# MKRCANShieldV2_0.net
KiCad netlist of a schematic drawn in EAGLE
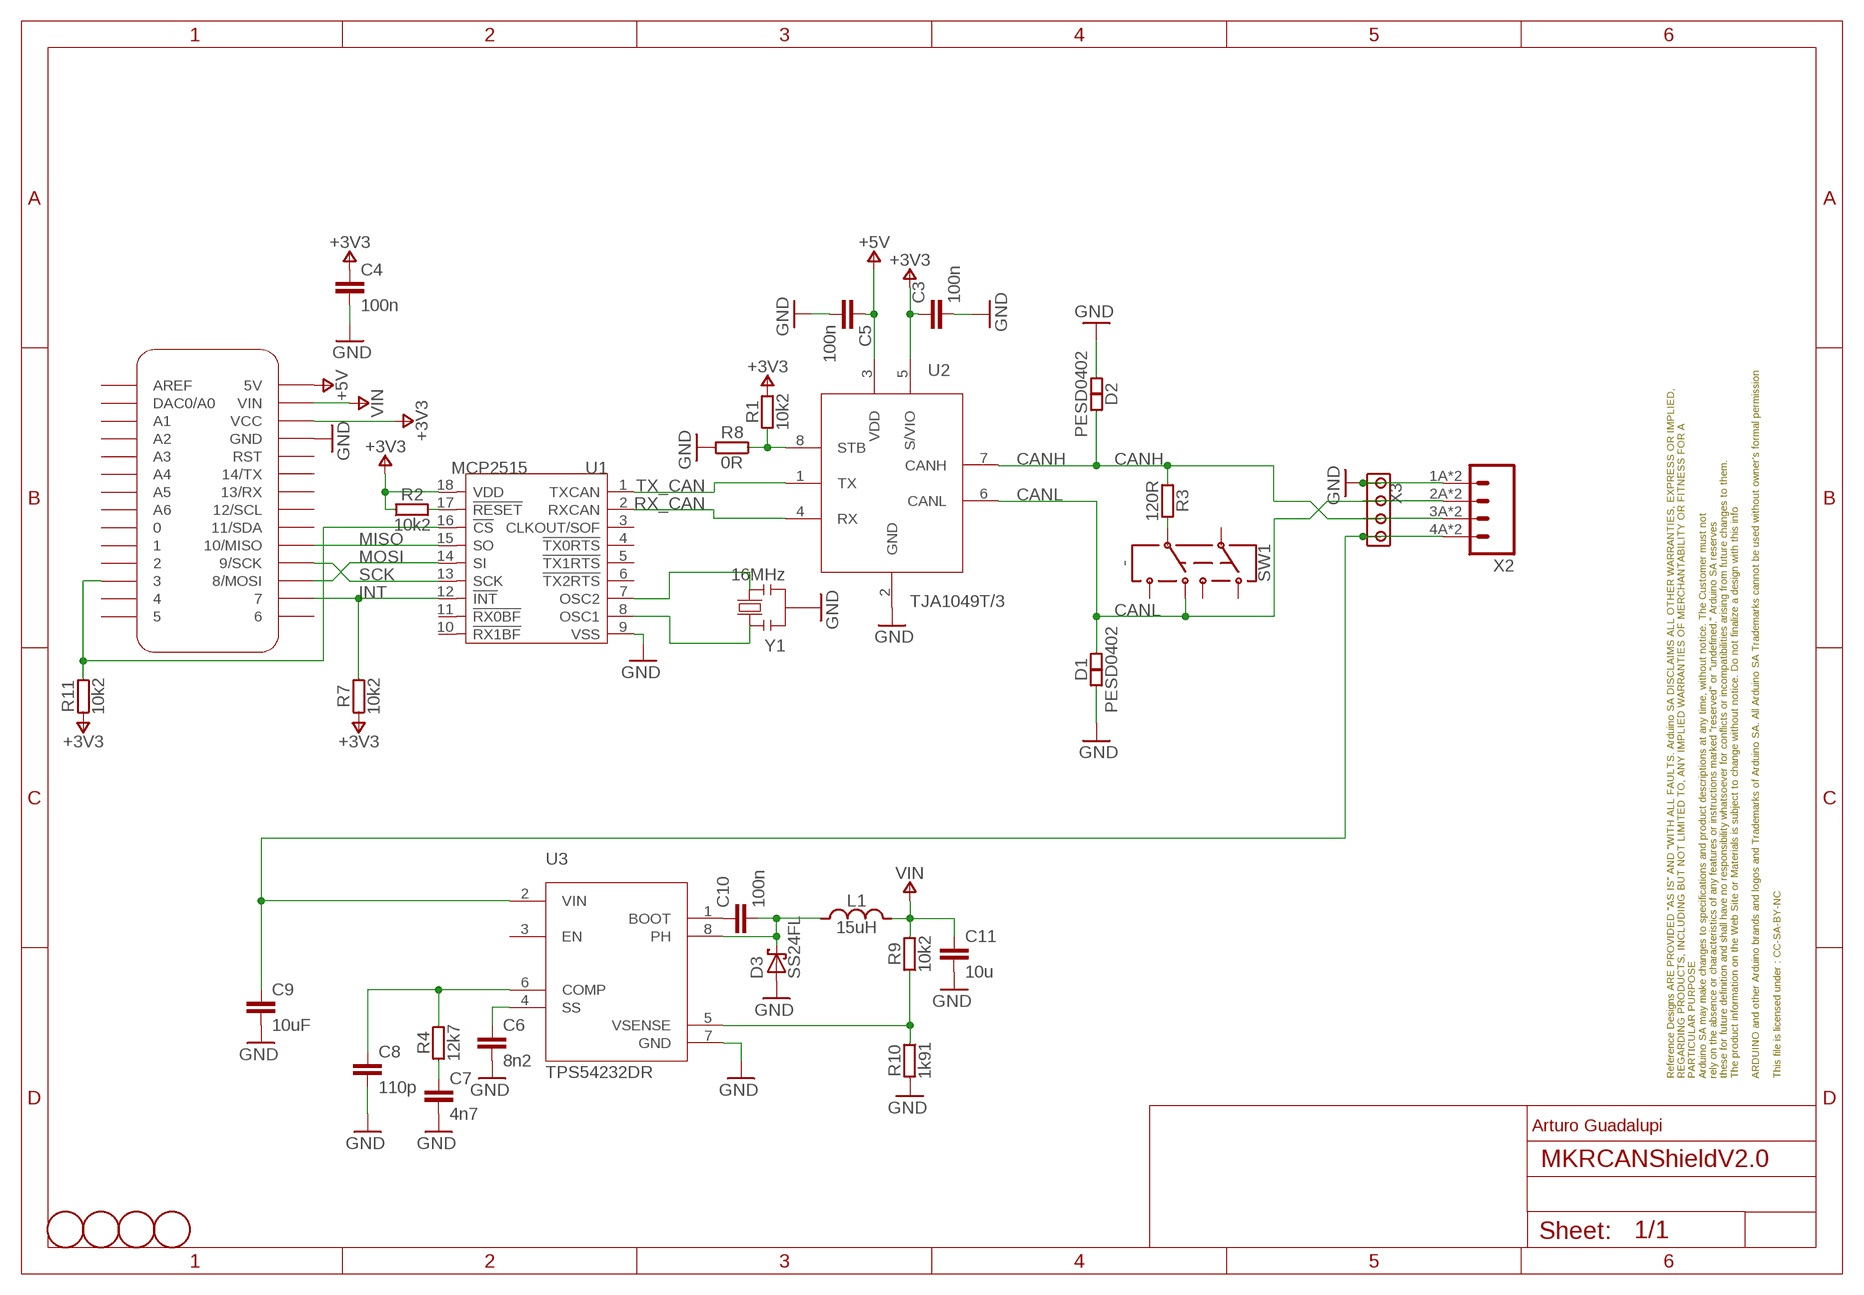
[diagram p0: schematic, sheet 1]

(export (version "E")
  (design (tool "Eeschema 10.0.6"))
  (components
    (comp (ref "C3")
      (value "100n")
      (footprint "eagle-import:0402-1005X55N")
      (fields (field (name "MANUFACTURER") "TDK"))
      (libsource (lib "eagle-import") (part "C-0402-100NF"))
    )
    (comp (ref "C4")
      (value "100n")
      (footprint "eagle-import:0402-1005X55N")
      (fields (field (name "MANUFACTURER") "TDK"))
      (libsource (lib "eagle-import") (part "C-0402-100NF"))
    )
    (comp (ref "C5")
      (value "100n")
      (footprint "eagle-import:0402-1005X55N")
      (fields (field (name "MANUFACTURER") "TDK"))
      (libsource (lib "eagle-import") (part "C-0402-100NF"))
    )
    (comp (ref "C6")
      (value "8n2")
      (footprint "eagle-import:0402-1005X55N")
      (fields (field (name "MANUFACTURER") "Yageo"))
      (libsource (lib "eagle-import") (part "C-0402-8N2"))
    )
    (comp (ref "C7")
      (value "4n7")
      (footprint "eagle-import:0402-1005X55N")
      (fields (field (name "MANUFACTURER") "Murata"))
      (libsource (lib "eagle-import") (part "C-0402-4N7"))
    )
    (comp (ref "C8")
      (value "110p")
      (footprint "eagle-import:0402-1005X55N")
      (fields (field (name "MANUFACTURER") "Murata"))
      (libsource (lib "eagle-import") (part "C-0402-110P"))
    )
    (comp (ref "C9")
      (value "10uF")
      (footprint "eagle-import:C1206")
      (fields (field (name "MANUFACTURER") "TDK Corporation"))
      (libsource (lib "eagle-import") (part "C-1206-10UF"))
    )
    (comp (ref "C10")
      (value "100n")
      (footprint "eagle-import:0402-1005X55N")
      (fields (field (name "MANUFACTURER") "TDK"))
      (libsource (lib "eagle-import") (part "C-0402-100NF"))
    )
    (comp (ref "C11")
      (value "10u")
      (footprint "eagle-import:0603-1608X90N")
      (fields (field (name "MANUFACTURER") "Murata"))
      (libsource (lib "eagle-import") (part "C-0603-10UF"))
    )
    (comp (ref "D1")
      (value "PESD0402")
      (footprint "eagle-import:0402-1005X55N")
      (fields (field (name "MANUFACTURER") "Littlefuse"))
      (libsource (lib "eagle-import") (part "PESD"))
    )
    (comp (ref "D2")
      (value "PESD0402")
      (footprint "eagle-import:0402-1005X55N")
      (fields (field (name "MANUFACTURER") "Littlefuse"))
      (libsource (lib "eagle-import") (part "PESD"))
    )
    (comp (ref "D3")
      (value "SS24FL")
      (footprint "eagle-import:SOD123F")
      (fields (field (name "MANUFACTURER") "Fairchild"))
      (libsource (lib "eagle-import") (part "SS24FL"))
    )
    (comp (ref "FRAME1")
      (value "DNP")
      (footprint "eagle-import:FRAME")
      (libsource (lib "eagle-import") (part "A4L-LOC"))
    )
    (comp (ref "L1")
      (value "15uH")
      (footprint "eagle-import:SRN6045")
      (fields (field (name "MANUFACTURER") "Bourns"))
      (libsource (lib "eagle-import") (part "LSRN"))
    )
    (comp (ref "MKR1")
      (value "-")
      (footprint "eagle-import:MKRBOARD-NH")
      (libsource (lib "eagle-import") (part "MKRBOARD"))
    )
    (comp (ref "R1")
      (value "10k2")
      (footprint "eagle-import:0402-1005X55N")
      (fields (field (name "MANUFACTURER") "Yageo"))
      (libsource (lib "eagle-import") (part "R-0402-10K2"))
    )
    (comp (ref "R2")
      (value "10k2")
      (footprint "eagle-import:0402-1005X55N")
      (fields (field (name "MANUFACTURER") "Yageo"))
      (libsource (lib "eagle-import") (part "R-0402-10K2"))
    )
    (comp (ref "R3")
      (value "120R")
      (footprint "eagle-import:0402-1005X55N")
      (fields (field (name "MANUFACTURER") "Yageo"))
      (libsource (lib "eagle-import") (part "R-0402-120R"))
    )
    (comp (ref "R4")
      (value "12k7")
      (footprint "eagle-import:0402-1005X55N")
      (fields (field (name "MANUFACTURER") "Yageo"))
      (libsource (lib "eagle-import") (part "R-0402-12K7"))
    )
    (comp (ref "R7")
      (value "10k2")
      (footprint "eagle-import:0402-1005X55N")
      (fields (field (name "MANUFACTURER") "Yageo"))
      (libsource (lib "eagle-import") (part "R-0402-10K2"))
    )
    (comp (ref "R8")
      (value "0R")
      (footprint "eagle-import:0402-1005X55N")
      (fields (field (name "MANUFACTURER") "Yageo"))
      (libsource (lib "eagle-import") (part "R-0402-0R"))
    )
    (comp (ref "R9")
      (value "10k2")
      (footprint "eagle-import:0402-1005X55N")
      (fields (field (name "MANUFACTURER") "Yageo"))
      (libsource (lib "eagle-import") (part "R-0402-10K2"))
    )
    (comp (ref "R10")
      (value "1k91")
      (footprint "eagle-import:0402-1005X55N")
      (fields (field (name "MANUFACTURER") "Yageo"))
      (libsource (lib "eagle-import") (part "R-0402-1K91"))
    )
    (comp (ref "R11")
      (value "10k2")
      (footprint "eagle-import:0402-1005X55N")
      (fields (field (name "MANUFACTURER") "Yageo"))
      (libsource (lib "eagle-import") (part "R-0402-10K2"))
    )
    (comp (ref "SW1")
      (value "-")
      (footprint "eagle-import:CL-SB-22A")
      (fields (field (name "MANUFACTURER") "Copal Electronics"))
      (libsource (lib "eagle-import") (part "CL-SB-22A-02T"))
    )
    (comp (ref "U$1")
      (value "DNP")
      (footprint "eagle-import:FD-1-1.5")
      (libsource (lib "eagle-import") (part "FIDUCIAL-1.5MM"))
    )
    (comp (ref "U$4")
      (value "DNP")
      (footprint "eagle-import:FD-1-1.5")
      (libsource (lib "eagle-import") (part "FIDUCIAL-1.5MM"))
    )
    (comp (ref "U$6")
      (value "DNP")
      (footprint "eagle-import:FD-1-1.5")
      (libsource (lib "eagle-import") (part "FIDUCIAL-1.5MM"))
    )
    (comp (ref "U$13")
      (value "DNP")
      (footprint "eagle-import:FD-1-1.5")
      (libsource (lib "eagle-import") (part "FIDUCIAL-1.5MM"))
    )
    (comp (ref "U1")
      (value "MCP2515")
      (footprint "eagle-import:SOIC18")
      (fields (field (name "MANUFACTURER") "Microchip"))
      (libsource (lib "eagle-import") (part "MCP2515-SOIC18"))
    )
    (comp (ref "U2")
      (value "TJA1049T/3")
      (footprint "eagle-import:SO08")
      (fields (field (name "MANUFACTURER") "NXP"))
      (libsource (lib "eagle-import") (part "TJA104X-9T/3"))
    )
    (comp (ref "U3")
      (value "TPS54232DR")
      (footprint "eagle-import:SO08")
      (fields (field (name "MANUFACTURER") "Texas Instruments"))
      (libsource (lib "eagle-import") (part "TPS54232"))
    )
    (comp (ref "X2")
      (value "DNP")
      (footprint "eagle-import:SPTAF1_4-3.5-IL")
      (libsource (lib "eagle-import") (part "3.5MM-PCBPRESS-DNP"))
    )
    (comp (ref "X3")
      (value "-")
      (footprint "eagle-import:MODULINO-4")
      (fields (field (name "MANUFACTURER") "On Shore"))
      (libsource (lib "eagle-import") (part "SCREW4X2.54"))
    )
    (comp (ref "Y1")
      (value "16MHz")
      (footprint "eagle-import:RESONATOR")
      (fields (field (name "MANUFACTURER") "Murata"))
      (libsource (lib "eagle-import") (part "RESONATORMU-16MHZ"))
    )
  )
  (nets
    (net (code "1") (name "+3V3") (class "Default")
      (node (ref "C3") (pin "1") (pinfunction "1_1") (pintype "passive"))
      (node (ref "C4") (pin "1") (pinfunction "1_1") (pintype "passive"))
      (node (ref "MKR1") (pin "VCC") (pinfunction "VCC_VCC") (pintype "bidirectional"))
      (node (ref "R1") (pin "2") (pinfunction "2_2") (pintype "passive"))
      (node (ref "R11") (pin "2") (pinfunction "2_2") (pintype "passive"))
      (node (ref "R2") (pin "2") (pinfunction "2_2") (pintype "passive"))
      (node (ref "R7") (pin "2") (pinfunction "2_2") (pintype "passive"))
      (node (ref "U1") (pin "18") (pinfunction "VDD_18") (pintype "power_in"))
      (node (ref "U2") (pin "5") (pinfunction "S/VIO_5") (pintype "bidirectional"))
    )
    (net (code "2") (name "+5V") (class "Default")
      (node (ref "C5") (pin "1") (pinfunction "1_1") (pintype "passive"))
      (node (ref "MKR1") (pin "5V") (pinfunction "5V_5V") (pintype "bidirectional"))
      (node (ref "U2") (pin "3") (pinfunction "VDD_3") (pintype "power_in"))
    )
    (net (code "3") (name "/CANH") (class "Default")
      (node (ref "D2") (pin "2") (pinfunction "2_2") (pintype "passive"))
      (node (ref "R3") (pin "1") (pinfunction "1_1") (pintype "passive"))
      (node (ref "U2") (pin "7") (pinfunction "CANH_7") (pintype "bidirectional"))
      (node (ref "X2") (pin "3A") (pinfunction "3_3A") (pintype "passive"))
      (node (ref "X2") (pin "3B") (pinfunction "3_3B") (pintype "passive"))
      (node (ref "X3") (pin "3") (pinfunction "3_3") (pintype "passive"))
    )
    (net (code "4") (name "/CANL") (class "Default")
      (node (ref "D1") (pin "2") (pinfunction "2_2") (pintype "passive"))
      (node (ref "SW1") (pin "P$4") (pinfunction "4_P$4") (pintype "bidirectional"))
      (node (ref "U2") (pin "6") (pinfunction "CANL_6") (pintype "bidirectional"))
      (node (ref "X2") (pin "2A") (pinfunction "2_2A") (pintype "passive"))
      (node (ref "X2") (pin "2B") (pinfunction "2_2B") (pintype "passive"))
      (node (ref "X3") (pin "2") (pinfunction "2_2") (pintype "passive"))
    )
    (net (code "5") (name "/INT") (class "Default")
      (node (ref "MKR1") (pin "7") (pinfunction "7_7") (pintype "bidirectional"))
      (node (ref "R7") (pin "1") (pinfunction "1_1") (pintype "passive"))
      (node (ref "U1") (pin "12") (pinfunction "~{INT}_12") (pintype "output"))
    )
    (net (code "6") (name "/MISO") (class "Default")
      (node (ref "MKR1") (pin "10") (pinfunction "10/MISO_10") (pintype "bidirectional"))
      (node (ref "U1") (pin "15") (pinfunction "SO_15") (pintype "output"))
    )
    (net (code "7") (name "/MOSI") (class "Default")
      (node (ref "MKR1") (pin "8") (pinfunction "8/MOSI_8") (pintype "bidirectional"))
      (node (ref "U1") (pin "14") (pinfunction "SI_14") (pintype "input"))
    )
    (net (code "8") (name "/RX_CAN") (class "Default")
      (node (ref "U1") (pin "2") (pinfunction "RXCAN_2") (pintype "input"))
      (node (ref "U2") (pin "4") (pinfunction "RX_4") (pintype "output"))
    )
    (net (code "9") (name "/SCK") (class "Default")
      (node (ref "MKR1") (pin "9") (pinfunction "9/SCK_9") (pintype "bidirectional"))
      (node (ref "U1") (pin "13") (pinfunction "SCK_13") (pintype "input"))
    )
    (net (code "10") (name "/TX_CAN") (class "Default")
      (node (ref "U1") (pin "1") (pinfunction "TXCAN_1") (pintype "output"))
      (node (ref "U2") (pin "1") (pinfunction "TX_1") (pintype "input"))
    )
    (net (code "11") (name "GND") (class "Default")
      (node (ref "C11") (pin "2") (pinfunction "2_2") (pintype "passive"))
      (node (ref "C3") (pin "2") (pinfunction "2_2") (pintype "passive"))
      (node (ref "C4") (pin "2") (pinfunction "2_2") (pintype "passive"))
      (node (ref "C5") (pin "2") (pinfunction "2_2") (pintype "passive"))
      (node (ref "C6") (pin "2") (pinfunction "2_2") (pintype "passive"))
      (node (ref "C7") (pin "2") (pinfunction "2_2") (pintype "passive"))
      (node (ref "C8") (pin "2") (pinfunction "2_2") (pintype "passive"))
      (node (ref "C9") (pin "2") (pinfunction "2_2") (pintype "passive"))
      (node (ref "D1") (pin "1") (pinfunction "1_1") (pintype "passive"))
      (node (ref "D2") (pin "1") (pinfunction "1_1") (pintype "passive"))
      (node (ref "D3") (pin "A") (pinfunction "A_A") (pintype "passive"))
      (node (ref "MKR1") (pin "GND") (pinfunction "GND_GND") (pintype "bidirectional"))
      (node (ref "R10") (pin "1") (pinfunction "1_1") (pintype "passive"))
      (node (ref "R8") (pin "1") (pinfunction "1_1") (pintype "passive"))
      (node (ref "U1") (pin "9") (pinfunction "VSS_9") (pintype "power_in"))
      (node (ref "U2") (pin "2") (pinfunction "GND_2") (pintype "power_in"))
      (node (ref "U3") (pin "7") (pinfunction "GND_7") (pintype "bidirectional"))
      (node (ref "X2") (pin "1A") (pinfunction "1_1A") (pintype "passive"))
      (node (ref "X2") (pin "1B") (pinfunction "1_1B") (pintype "passive"))
      (node (ref "X3") (pin "1") (pinfunction "1_1") (pintype "passive"))
      (node (ref "Y1") (pin "2") (pinfunction "2_2") (pintype "passive"))
    )
    (net (code "12") (name "Net-(C7-Pad1)") (class "Default")
      (node (ref "C7") (pin "1") (pinfunction "1_1") (pintype "passive"))
      (node (ref "R4") (pin "1") (pinfunction "1_1") (pintype "passive"))
    )
    (net (code "13") (name "Net-(SW1-5)") (class "Default")
      (node (ref "R3") (pin "2") (pinfunction "2_2") (pintype "passive"))
      (node (ref "SW1") (pin "P$5") (pinfunction "5_P$5") (pintype "bidirectional"))
    )
    (net (code "14") (name "Net-(U1-OSC1)") (class "Default")
      (node (ref "U1") (pin "8") (pinfunction "OSC1_8") (pintype "input"))
      (node (ref "Y1") (pin "1") (pinfunction "1_1") (pintype "passive"))
    )
    (net (code "15") (name "Net-(U1-OSC2)") (class "Default")
      (node (ref "U1") (pin "7") (pinfunction "OSC2_7") (pintype "output"))
      (node (ref "Y1") (pin "3") (pinfunction "3_3") (pintype "passive"))
    )
    (net (code "16") (name "Net-(U1-~{CS})") (class "Default")
      (node (ref "MKR1") (pin "3") (pinfunction "3_3") (pintype "bidirectional"))
      (node (ref "R11") (pin "1") (pinfunction "1_1") (pintype "passive"))
      (node (ref "U1") (pin "16") (pinfunction "~{CS}_16") (pintype "input"))
    )
    (net (code "17") (name "Net-(U1-~{RESET})") (class "Default")
      (node (ref "R2") (pin "1") (pinfunction "1_1") (pintype "passive"))
      (node (ref "U1") (pin "17") (pinfunction "~{RESET}_17") (pintype "input"))
    )
    (net (code "18") (name "Net-(U2-STB)") (class "Default")
      (node (ref "R1") (pin "1") (pinfunction "1_1") (pintype "passive"))
      (node (ref "R8") (pin "2") (pinfunction "2_2") (pintype "passive"))
      (node (ref "U2") (pin "8") (pinfunction "STB_8") (pintype "input"))
    )
    (net (code "19") (name "Net-(U3-BOOT)") (class "Default")
      (node (ref "C10") (pin "1") (pinfunction "1_1") (pintype "passive"))
      (node (ref "U3") (pin "1") (pinfunction "BOOT_1") (pintype "bidirectional"))
    )
    (net (code "20") (name "Net-(U3-COMP)") (class "Default")
      (node (ref "C8") (pin "1") (pinfunction "1_1") (pintype "passive"))
      (node (ref "R4") (pin "2") (pinfunction "2_2") (pintype "passive"))
      (node (ref "U3") (pin "6") (pinfunction "COMP_6") (pintype "bidirectional"))
    )
    (net (code "21") (name "Net-(U3-PH)") (class "Default")
      (node (ref "C10") (pin "2") (pinfunction "2_2") (pintype "passive"))
      (node (ref "D3") (pin "C") (pinfunction "C_C") (pintype "passive"))
      (node (ref "L1") (pin "1") (pinfunction "1_1") (pintype "passive"))
      (node (ref "U3") (pin "8") (pinfunction "PH_8") (pintype "bidirectional"))
    )
    (net (code "22") (name "Net-(U3-SS)") (class "Default")
      (node (ref "C6") (pin "1") (pinfunction "1_1") (pintype "passive"))
      (node (ref "U3") (pin "4") (pinfunction "SS_4") (pintype "bidirectional"))
    )
    (net (code "23") (name "Net-(U3-VIN)") (class "Default")
      (node (ref "C9") (pin "1") (pinfunction "1_1") (pintype "passive"))
      (node (ref "U3") (pin "2") (pinfunction "VIN_2") (pintype "bidirectional"))
      (node (ref "X2") (pin "4A") (pinfunction "4_4A") (pintype "passive"))
      (node (ref "X2") (pin "4B") (pinfunction "4_4B") (pintype "passive"))
      (node (ref "X3") (pin "4") (pinfunction "4_4") (pintype "passive"))
    )
    (net (code "24") (name "Net-(U3-VSENSE)") (class "Default")
      (node (ref "R10") (pin "2") (pinfunction "2_2") (pintype "passive"))
      (node (ref "R9") (pin "1") (pinfunction "1_1") (pintype "passive"))
      (node (ref "U3") (pin "5") (pinfunction "VSENSE_5") (pintype "bidirectional"))
    )
    (net (code "25") (name "VIN") (class "Default")
      (node (ref "C11") (pin "1") (pinfunction "1_1") (pintype "passive"))
      (node (ref "L1") (pin "2") (pinfunction "2_2") (pintype "passive"))
      (node (ref "MKR1") (pin "VIN") (pinfunction "VIN_VIN") (pintype "bidirectional"))
      (node (ref "R9") (pin "2") (pinfunction "2_2") (pintype "passive"))
    )
    (net (code "26") (name "unconnected-(MKR1-11{slash}SDA-Pad11)") (class "Default")
      (node (ref "MKR1") (pin "11") (pinfunction "11/SDA_11") (pintype "bidirectional"))
    )
    (net (code "27") (name "unconnected-(MKR1-12{slash}SCL-Pad12)") (class "Default")
      (node (ref "MKR1") (pin "12") (pinfunction "12/SCL_12") (pintype "bidirectional"))
    )
    (net (code "28") (name "unconnected-(MKR1-13{slash}RX-Pad13)") (class "Default")
      (node (ref "MKR1") (pin "13") (pinfunction "13/RX_13") (pintype "bidirectional"))
    )
    (net (code "29") (name "unconnected-(MKR1-14{slash}TX-Pad14)") (class "Default")
      (node (ref "MKR1") (pin "14") (pinfunction "14/TX_14") (pintype "bidirectional"))
    )
    (net (code "30") (name "unconnected-(MKR1-DAC0{slash}A0-PadA0)") (class "Default")
      (node (ref "MKR1") (pin "A0") (pinfunction "DAC0/A0_A0") (pintype "bidirectional"))
    )
    (net (code "31") (name "unconnected-(MKR1-Pad0)") (class "Default")
      (node (ref "MKR1") (pin "0") (pinfunction "0_0") (pintype "bidirectional"))
    )
    (net (code "32") (name "unconnected-(MKR1-Pad1)") (class "Default")
      (node (ref "MKR1") (pin "1") (pinfunction "1_1") (pintype "bidirectional"))
    )
    (net (code "33") (name "unconnected-(MKR1-Pad2)") (class "Default")
      (node (ref "MKR1") (pin "2") (pinfunction "2_2") (pintype "bidirectional"))
    )
    (net (code "34") (name "unconnected-(MKR1-Pad4)") (class "Default")
      (node (ref "MKR1") (pin "4") (pinfunction "4_4") (pintype "bidirectional"))
    )
    (net (code "35") (name "unconnected-(MKR1-Pad5)") (class "Default")
      (node (ref "MKR1") (pin "5") (pinfunction "5_5") (pintype "bidirectional"))
    )
    (net (code "36") (name "unconnected-(MKR1-Pad6)") (class "Default")
      (node (ref "MKR1") (pin "6") (pinfunction "6_6") (pintype "bidirectional"))
    )
    (net (code "37") (name "unconnected-(MKR1-PadA1)") (class "Default")
      (node (ref "MKR1") (pin "A1") (pinfunction "A1_A1") (pintype "bidirectional"))
    )
    (net (code "38") (name "unconnected-(MKR1-PadA2)") (class "Default")
      (node (ref "MKR1") (pin "A2") (pinfunction "A2_A2") (pintype "bidirectional"))
    )
    (net (code "39") (name "unconnected-(MKR1-PadA3)") (class "Default")
      (node (ref "MKR1") (pin "A3") (pinfunction "A3_A3") (pintype "bidirectional"))
    )
    (net (code "40") (name "unconnected-(MKR1-PadA4)") (class "Default")
      (node (ref "MKR1") (pin "A4") (pinfunction "A4_A4") (pintype "bidirectional"))
    )
    (net (code "41") (name "unconnected-(MKR1-PadA5)") (class "Default")
      (node (ref "MKR1") (pin "A5") (pinfunction "A5_A5") (pintype "bidirectional"))
    )
    (net (code "42") (name "unconnected-(MKR1-PadA6)") (class "Default")
      (node (ref "MKR1") (pin "A6") (pinfunction "A6_A6") (pintype "bidirectional"))
    )
    (net (code "43") (name "unconnected-(MKR1-PadAREF)") (class "Default")
      (node (ref "MKR1") (pin "AREF") (pinfunction "AREF_AREF") (pintype "bidirectional"))
    )
    (net (code "44") (name "unconnected-(MKR1-PadRST)") (class "Default")
      (node (ref "MKR1") (pin "RST") (pinfunction "RST_RST") (pintype "bidirectional"))
    )
    (net (code "45") (name "unconnected-(SW1-1-PadP$1)") (class "Default")
      (node (ref "SW1") (pin "P$1") (pinfunction "1_P$1") (pintype "bidirectional"))
    )
    (net (code "46") (name "unconnected-(SW1-2-PadP$2)") (class "Default")
      (node (ref "SW1") (pin "P$2") (pinfunction "2_P$2") (pintype "bidirectional"))
    )
    (net (code "47") (name "unconnected-(SW1-3-PadP$3)") (class "Default")
      (node (ref "SW1") (pin "P$3") (pinfunction "3_P$3") (pintype "bidirectional"))
    )
    (net (code "48") (name "unconnected-(SW1-6-PadP$6)") (class "Default")
      (node (ref "SW1") (pin "P$6") (pinfunction "6_P$6") (pintype "bidirectional"))
    )
    (net (code "49") (name "unconnected-(U1-CLKOUT{slash}SOF-Pad3)") (class "Default")
      (node (ref "U1") (pin "3") (pinfunction "CLKOUT/SOF_3") (pintype "output"))
    )
    (net (code "50") (name "unconnected-(U1-~{RX0BF}-Pad11)") (class "Default")
      (node (ref "U1") (pin "11") (pinfunction "~{RX0BF}_11") (pintype "output"))
    )
    (net (code "51") (name "unconnected-(U1-~{RX1BF}-Pad10)") (class "Default")
      (node (ref "U1") (pin "10") (pinfunction "~{RX1BF}_10") (pintype "output"))
    )
    (net (code "52") (name "unconnected-(U1-~{TX0RTS}-Pad4)") (class "Default")
      (node (ref "U1") (pin "4") (pinfunction "~{TX0RTS}_4") (pintype "input"))
    )
    (net (code "53") (name "unconnected-(U1-~{TX1RTS}-Pad5)") (class "Default")
      (node (ref "U1") (pin "5") (pinfunction "~{TX1RTS}_5") (pintype "input"))
    )
    (net (code "54") (name "unconnected-(U1-~{TX2RTS}-Pad6)") (class "Default")
      (node (ref "U1") (pin "6") (pinfunction "~{TX2RTS}_6") (pintype "input"))
    )
    (net (code "55") (name "unconnected-(U3-EN-Pad3)") (class "Default")
      (node (ref "U3") (pin "3") (pinfunction "EN_3") (pintype "bidirectional"))
    )
  )
)
